# protect_circuit.net
KiCad netlist of a schematic drawn in Altium Designer
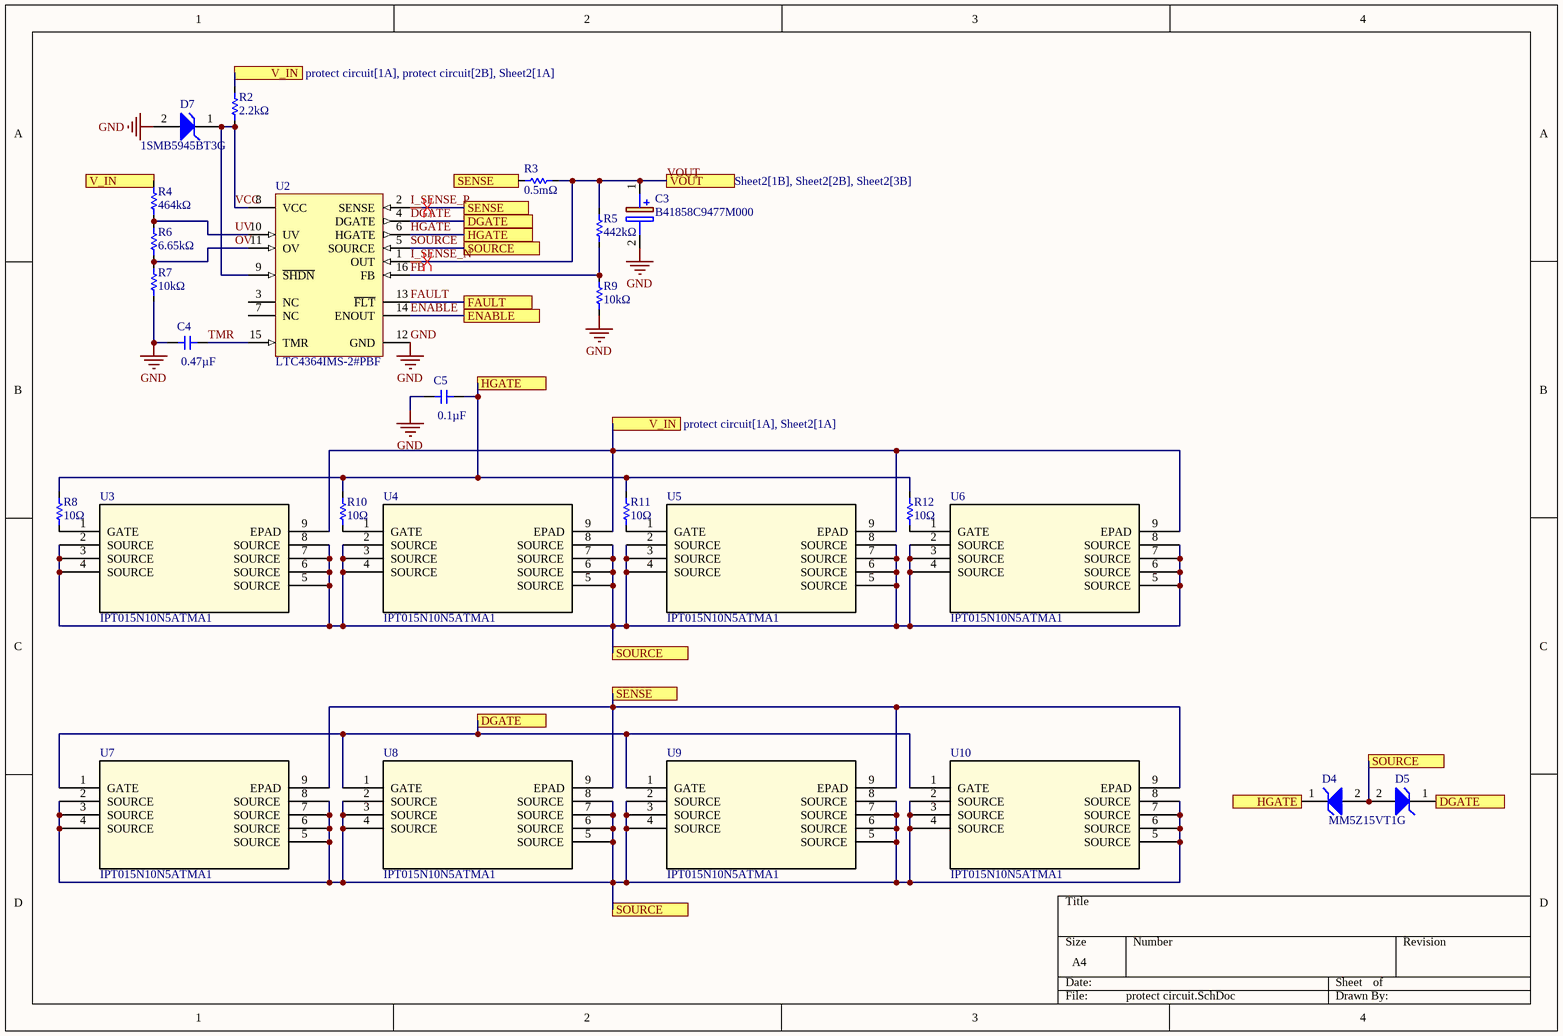
[diagram p0: protect circuit.SchDoc]

(export (version "E")
  (design (tool "Eeschema 10.0.6"))
  (components
    (comp (ref "C3")
      (value "B41858C9477M000")
      (footprint "SamacSys:CAPPRD750W90D1800H3700")
      (description "Capacitor Polarised")
      (fields (field (name "MOUSER PART NUMBER") "871-B41858C9477M"))
      (libsource (lib "*") (part "B41858C9477M000"))
    )
    (comp (ref "C4")
      (value "non-polar_Capacitor")
      (footprint "1210")
      (description "SMD type ceramic capacitor")
      (fields
        (field (name "VOLTAGE") "50V")
        (field (name "CAPACITANCE") "0.47µF")
        (field (name "SOURCE") "robit_passive.SchLib")
      )
      (libsource (lib "robit circuit") (part "Capacitor"))
    )
    (comp (ref "C5")
      (value "non-polar_Capacitor")
      (footprint "1210")
      (description "SMD type ceramic capacitor")
      (fields
        (field (name "VOLTAGE") "50V")
        (field (name "CAPACITANCE") "0.1µF")
        (field (name "SOURCE") "robit_passive.SchLib")
      )
      (libsource (lib "robit circuit") (part "Capacitor"))
    )
    (comp (ref "D4")
      (value "MM5Z15VT1G")
      (footprint "ONSC-SOD-523-2-502-01_V")
      (description "Zener Voltage Regulator, 500 mW, 2-Pin SOD-523, Pb-Free, Tape and Reel")
      (fields (field (name "MANUFACTURER") "On Semiconductor"))
      (libsource (lib "Altium Content Vault") (part "ONSC-K1A2-2"))
    )
    (comp (ref "D5")
      (value "MM5Z15VT1G")
      (footprint "ONSC-SOD-523-2-502-01_V")
      (description "Zener Voltage Regulator, 500 mW, 2-Pin SOD-523, Pb-Free, Tape and Reel")
      (fields (field (name "MANUFACTURER") "On Semiconductor"))
      (libsource (lib "Altium Content Vault") (part "ONSC-K1A2-2"))
    )
    (comp (ref "D7")
      (value "1SMB5945BT3G")
      (footprint "ONSC-SMB-2-403A-03_H_V")
      (description "3 W Zener Voltage Regulator, 2-Pin SMB, Pb-Free, Tape and Reel")
      (fields (field (name "MANUFACTURER") "On Semiconductor"))
      (libsource (lib "Altium Content Vault") (part "ONSC-K1A2-2"))
    )
    (comp (ref "R2") (value "2.2kΩ") (footprint "SMD_2512") (libsource (lib "Resistor") (part "Resistor")))
    (comp (ref "R3") (value "0.5mΩ") (footprint "SMD_2512") (libsource (lib "Resistor") (part "Resistor")))
    (comp (ref "R4") (value "464kΩ") (footprint "SMD_0603") (libsource (lib "Resistor") (part "Resistor")))
    (comp (ref "R5") (value "442kΩ") (footprint "SMD_0603") (libsource (lib "Resistor") (part "Resistor")))
    (comp (ref "R6") (value "6.65kΩ") (footprint "SMD_0603") (libsource (lib "Resistor") (part "Resistor")))
    (comp (ref "R7") (value "10kΩ") (footprint "SMD_0603") (libsource (lib "Resistor") (part "Resistor")))
    (comp (ref "R8") (value "10Ω") (footprint "SMD_0603") (libsource (lib "Resistor") (part "Resistor")))
    (comp (ref "R9") (value "10kΩ") (footprint "SMD_0603") (libsource (lib "Resistor") (part "Resistor")))
    (comp (ref "R10") (value "10Ω") (footprint "SMD_0603") (libsource (lib "Resistor") (part "Resistor")))
    (comp (ref "R11") (value "10Ω") (footprint "SMD_0603") (libsource (lib "Resistor") (part "Resistor")))
    (comp (ref "R12") (value "10Ω") (footprint "SMD_0603") (libsource (lib "Resistor") (part "Resistor")))
    (comp (ref "U2")
      (value "LTC4364IMS-2#PBF")
      (footprint "LT-MS-16_M")
      (description "Surge Stopper with Ideal Diode, 4 to 80 V Vin, 16-pin SOP (MS-16), -40 to 85 degC, Pb-Free")
      (fields (field (name "MANUFACTURER") "Linear Technology"))
      (libsource (lib "Altium Content Vault") (part "LT-LTC4364-S-16"))
    )
    (comp (ref "U3")
      (value "IPT015N10N5ATMA1")
      (footprint "PG-HSOF-8-1_INF")
      (fields (field (name "COPYRIGHT") "Copyright (C) 2025 Ultra Librarian. All rights reserved."))
      (libsource (lib "IPT015N10N5ATMA1") (part "IPT015N10N5ATMA1"))
    )
    (comp (ref "U4")
      (value "IPT015N10N5ATMA1")
      (footprint "PG-HSOF-8-1_INF")
      (fields (field (name "COPYRIGHT") "Copyright (C) 2025 Ultra Librarian. All rights reserved."))
      (libsource (lib "IPT015N10N5ATMA1") (part "IPT015N10N5ATMA1"))
    )
    (comp (ref "U5")
      (value "IPT015N10N5ATMA1")
      (footprint "PG-HSOF-8-1_INF")
      (fields (field (name "COPYRIGHT") "Copyright (C) 2025 Ultra Librarian. All rights reserved."))
      (libsource (lib "IPT015N10N5ATMA1") (part "IPT015N10N5ATMA1"))
    )
    (comp (ref "U6")
      (value "IPT015N10N5ATMA1")
      (footprint "PG-HSOF-8-1_INF")
      (fields (field (name "COPYRIGHT") "Copyright (C) 2025 Ultra Librarian. All rights reserved."))
      (libsource (lib "IPT015N10N5ATMA1") (part "IPT015N10N5ATMA1"))
    )
    (comp (ref "U7")
      (value "IPT015N10N5ATMA1")
      (footprint "PG-HSOF-8-1_INF")
      (fields (field (name "COPYRIGHT") "Copyright (C) 2025 Ultra Librarian. All rights reserved."))
      (libsource (lib "IPT015N10N5ATMA1") (part "IPT015N10N5ATMA1"))
    )
    (comp (ref "U8")
      (value "IPT015N10N5ATMA1")
      (footprint "PG-HSOF-8-1_INF")
      (fields (field (name "COPYRIGHT") "Copyright (C) 2025 Ultra Librarian. All rights reserved."))
      (libsource (lib "IPT015N10N5ATMA1") (part "IPT015N10N5ATMA1"))
    )
    (comp (ref "U9")
      (value "IPT015N10N5ATMA1")
      (footprint "PG-HSOF-8-1_INF")
      (fields (field (name "COPYRIGHT") "Copyright (C) 2025 Ultra Librarian. All rights reserved."))
      (libsource (lib "IPT015N10N5ATMA1") (part "IPT015N10N5ATMA1"))
    )
    (comp (ref "U10")
      (value "IPT015N10N5ATMA1")
      (footprint "PG-HSOF-8-1_INF")
      (fields (field (name "COPYRIGHT") "Copyright (C) 2025 Ultra Librarian. All rights reserved."))
      (libsource (lib "IPT015N10N5ATMA1") (part "IPT015N10N5ATMA1"))
    )
  )
  (nets
    (net (code "1") (name "/DGATE") (class "Default")
      (node (ref "D5") (pin "1") (pinfunction "K_1") (pintype "passive"))
      (node (ref "U10") (pin "1") (pinfunction "GATE_1") (pintype "passive"))
      (node (ref "U2") (pin "4") (pinfunction "DGATE_4") (pintype "output"))
      (node (ref "U7") (pin "1") (pinfunction "GATE_1") (pintype "passive"))
      (node (ref "U8") (pin "1") (pinfunction "GATE_1") (pintype "passive"))
      (node (ref "U9") (pin "1") (pinfunction "GATE_1") (pintype "passive"))
    )
    (net (code "2") (name "/ENABLE") (class "Default")
      (node (ref "U2") (pin "14") (pinfunction "ENOUT_14") (pintype "tri_state"))
    )
    (net (code "3") (name "/FAULT") (class "Default")
      (node (ref "U2") (pin "13") (pinfunction "~{FLT}_13") (pintype "tri_state"))
    )
    (net (code "4") (name "/FB") (class "Default")
      (node (ref "R5") (pin "2") (pinfunction "2_2") (pintype "passive"))
      (node (ref "R9") (pin "1") (pinfunction "1_1") (pintype "passive"))
      (node (ref "U2") (pin "16") (pinfunction "FB_16") (pintype "input"))
    )
    (net (code "5") (name "/HGATE") (class "Default")
      (node (ref "C5") (pin "2") (pinfunction "2_2") (pintype "passive"))
      (node (ref "D4") (pin "1") (pinfunction "K_1") (pintype "passive"))
      (node (ref "R10") (pin "1") (pinfunction "1_1") (pintype "passive"))
      (node (ref "R11") (pin "1") (pinfunction "1_1") (pintype "passive"))
      (node (ref "R12") (pin "1") (pinfunction "1_1") (pintype "passive"))
      (node (ref "R8") (pin "1") (pinfunction "1_1") (pintype "passive"))
      (node (ref "U2") (pin "6") (pinfunction "HGATE_6") (pintype "output"))
    )
    (net (code "6") (name "/I_SENSE_N") (class "Default")
      (node (ref "C3") (pin "1") (pinfunction "+_1") (pintype "passive"))
      (node (ref "R3") (pin "2") (pinfunction "2_2") (pintype "passive"))
      (node (ref "R5") (pin "1") (pinfunction "1_1") (pintype "passive"))
      (node (ref "U2") (pin "1") (pinfunction "OUT_1") (pintype "input"))
    )
    (net (code "7") (name "/I_SENSE_P") (class "Default")
      (node (ref "R3") (pin "1") (pinfunction "1_1") (pintype "passive"))
      (node (ref "U10") (pin "9") (pinfunction "EPAD_9") (pintype "passive"))
      (node (ref "U2") (pin "2") (pinfunction "SENSE_2") (pintype "input"))
      (node (ref "U7") (pin "9") (pinfunction "EPAD_9") (pintype "passive"))
      (node (ref "U8") (pin "9") (pinfunction "EPAD_9") (pintype "passive"))
      (node (ref "U9") (pin "9") (pinfunction "EPAD_9") (pintype "passive"))
    )
    (net (code "8") (name "/OV") (class "Default")
      (node (ref "R6") (pin "2") (pinfunction "2_2") (pintype "passive"))
      (node (ref "R7") (pin "1") (pinfunction "1_1") (pintype "passive"))
      (node (ref "U2") (pin "11") (pinfunction "OV_11") (pintype "input"))
    )
    (net (code "9") (name "/SOURCE") (class "Default")
      (node (ref "D4") (pin "2") (pinfunction "A_2") (pintype "passive"))
      (node (ref "D5") (pin "2") (pinfunction "A_2") (pintype "passive"))
      (node (ref "U10") (pin "2") (pinfunction "SOURCE_2") (pintype "passive"))
      (node (ref "U10") (pin "3") (pinfunction "SOURCE_3") (pintype "passive"))
      (node (ref "U10") (pin "4") (pinfunction "SOURCE_4") (pintype "passive"))
      (node (ref "U10") (pin "5") (pinfunction "SOURCE_5") (pintype "passive"))
      (node (ref "U10") (pin "6") (pinfunction "SOURCE_6") (pintype "passive"))
      (node (ref "U10") (pin "7") (pinfunction "SOURCE_7") (pintype "passive"))
      (node (ref "U10") (pin "8") (pinfunction "SOURCE_8") (pintype "passive"))
      (node (ref "U2") (pin "5") (pinfunction "SOURCE_5") (pintype "input"))
      (node (ref "U3") (pin "2") (pinfunction "SOURCE_2") (pintype "passive"))
      (node (ref "U3") (pin "3") (pinfunction "SOURCE_3") (pintype "passive"))
      (node (ref "U3") (pin "4") (pinfunction "SOURCE_4") (pintype "passive"))
      (node (ref "U3") (pin "5") (pinfunction "SOURCE_5") (pintype "passive"))
      (node (ref "U3") (pin "6") (pinfunction "SOURCE_6") (pintype "passive"))
      (node (ref "U3") (pin "7") (pinfunction "SOURCE_7") (pintype "passive"))
      (node (ref "U3") (pin "8") (pinfunction "SOURCE_8") (pintype "passive"))
      (node (ref "U4") (pin "2") (pinfunction "SOURCE_2") (pintype "passive"))
      (node (ref "U4") (pin "3") (pinfunction "SOURCE_3") (pintype "passive"))
      (node (ref "U4") (pin "4") (pinfunction "SOURCE_4") (pintype "passive"))
      (node (ref "U4") (pin "5") (pinfunction "SOURCE_5") (pintype "passive"))
      (node (ref "U4") (pin "6") (pinfunction "SOURCE_6") (pintype "passive"))
      (node (ref "U4") (pin "7") (pinfunction "SOURCE_7") (pintype "passive"))
      (node (ref "U4") (pin "8") (pinfunction "SOURCE_8") (pintype "passive"))
      (node (ref "U5") (pin "2") (pinfunction "SOURCE_2") (pintype "passive"))
      (node (ref "U5") (pin "3") (pinfunction "SOURCE_3") (pintype "passive"))
      (node (ref "U5") (pin "4") (pinfunction "SOURCE_4") (pintype "passive"))
      (node (ref "U5") (pin "5") (pinfunction "SOURCE_5") (pintype "passive"))
      (node (ref "U5") (pin "6") (pinfunction "SOURCE_6") (pintype "passive"))
      (node (ref "U5") (pin "7") (pinfunction "SOURCE_7") (pintype "passive"))
      (node (ref "U5") (pin "8") (pinfunction "SOURCE_8") (pintype "passive"))
      (node (ref "U6") (pin "2") (pinfunction "SOURCE_2") (pintype "passive"))
      (node (ref "U6") (pin "3") (pinfunction "SOURCE_3") (pintype "passive"))
      (node (ref "U6") (pin "4") (pinfunction "SOURCE_4") (pintype "passive"))
      (node (ref "U6") (pin "5") (pinfunction "SOURCE_5") (pintype "passive"))
      (node (ref "U6") (pin "6") (pinfunction "SOURCE_6") (pintype "passive"))
      (node (ref "U6") (pin "7") (pinfunction "SOURCE_7") (pintype "passive"))
      (node (ref "U6") (pin "8") (pinfunction "SOURCE_8") (pintype "passive"))
      (node (ref "U7") (pin "2") (pinfunction "SOURCE_2") (pintype "passive"))
      (node (ref "U7") (pin "3") (pinfunction "SOURCE_3") (pintype "passive"))
      (node (ref "U7") (pin "4") (pinfunction "SOURCE_4") (pintype "passive"))
      (node (ref "U7") (pin "5") (pinfunction "SOURCE_5") (pintype "passive"))
      (node (ref "U7") (pin "6") (pinfunction "SOURCE_6") (pintype "passive"))
      (node (ref "U7") (pin "7") (pinfunction "SOURCE_7") (pintype "passive"))
      (node (ref "U7") (pin "8") (pinfunction "SOURCE_8") (pintype "passive"))
      (node (ref "U8") (pin "2") (pinfunction "SOURCE_2") (pintype "passive"))
      (node (ref "U8") (pin "3") (pinfunction "SOURCE_3") (pintype "passive"))
      (node (ref "U8") (pin "4") (pinfunction "SOURCE_4") (pintype "passive"))
      (node (ref "U8") (pin "5") (pinfunction "SOURCE_5") (pintype "passive"))
      (node (ref "U8") (pin "6") (pinfunction "SOURCE_6") (pintype "passive"))
      (node (ref "U8") (pin "7") (pinfunction "SOURCE_7") (pintype "passive"))
      (node (ref "U8") (pin "8") (pinfunction "SOURCE_8") (pintype "passive"))
      (node (ref "U9") (pin "2") (pinfunction "SOURCE_2") (pintype "passive"))
      (node (ref "U9") (pin "3") (pinfunction "SOURCE_3") (pintype "passive"))
      (node (ref "U9") (pin "4") (pinfunction "SOURCE_4") (pintype "passive"))
      (node (ref "U9") (pin "5") (pinfunction "SOURCE_5") (pintype "passive"))
      (node (ref "U9") (pin "6") (pinfunction "SOURCE_6") (pintype "passive"))
      (node (ref "U9") (pin "7") (pinfunction "SOURCE_7") (pintype "passive"))
      (node (ref "U9") (pin "8") (pinfunction "SOURCE_8") (pintype "passive"))
    )
    (net (code "10") (name "/TMR") (class "Default")
      (node (ref "C4") (pin "2") (pinfunction "2_2") (pintype "passive"))
      (node (ref "U2") (pin "15") (pinfunction "TMR_15") (pintype "input"))
    )
    (net (code "11") (name "/UV") (class "Default")
      (node (ref "R4") (pin "2") (pinfunction "2_2") (pintype "passive"))
      (node (ref "R6") (pin "1") (pinfunction "1_1") (pintype "passive"))
      (node (ref "U2") (pin "10") (pinfunction "UV_10") (pintype "input"))
    )
    (net (code "12") (name "/VCC") (class "Default")
      (node (ref "D7") (pin "1") (pinfunction "K_1") (pintype "passive"))
      (node (ref "R2") (pin "2") (pinfunction "2_2") (pintype "passive"))
      (node (ref "U2") (pin "8") (pinfunction "VCC_8") (pintype "power_in"))
      (node (ref "U2") (pin "9") (pinfunction "~{SHDN}_9") (pintype "input"))
    )
    (net (code "13") (name "/V_IN") (class "Default")
      (node (ref "R2") (pin "1") (pinfunction "1_1") (pintype "passive"))
      (node (ref "R4") (pin "1") (pinfunction "1_1") (pintype "passive"))
      (node (ref "U3") (pin "9") (pinfunction "EPAD_9") (pintype "passive"))
      (node (ref "U4") (pin "9") (pinfunction "EPAD_9") (pintype "passive"))
      (node (ref "U5") (pin "9") (pinfunction "EPAD_9") (pintype "passive"))
      (node (ref "U6") (pin "9") (pinfunction "EPAD_9") (pintype "passive"))
    )
    (net (code "14") (name "GND") (class "Default")
      (node (ref "C3") (pin "2") (pinfunction "-_2") (pintype "passive"))
      (node (ref "C4") (pin "1") (pinfunction "1_1") (pintype "passive"))
      (node (ref "C5") (pin "1") (pinfunction "1_1") (pintype "passive"))
      (node (ref "D7") (pin "2") (pinfunction "A_2") (pintype "passive"))
      (node (ref "R7") (pin "2") (pinfunction "2_2") (pintype "passive"))
      (node (ref "R9") (pin "2") (pinfunction "2_2") (pintype "passive"))
      (node (ref "U2") (pin "12") (pinfunction "GND_12") (pintype "power_in"))
    )
    (net (code "15") (name "Net-(U3-GATE)") (class "Default")
      (node (ref "R8") (pin "2") (pinfunction "2_2") (pintype "passive"))
      (node (ref "U3") (pin "1") (pinfunction "GATE_1") (pintype "passive"))
    )
    (net (code "16") (name "Net-(U4-GATE)") (class "Default")
      (node (ref "R10") (pin "2") (pinfunction "2_2") (pintype "passive"))
      (node (ref "U4") (pin "1") (pinfunction "GATE_1") (pintype "passive"))
    )
    (net (code "17") (name "Net-(U5-GATE)") (class "Default")
      (node (ref "R11") (pin "2") (pinfunction "2_2") (pintype "passive"))
      (node (ref "U5") (pin "1") (pinfunction "GATE_1") (pintype "passive"))
    )
    (net (code "18") (name "Net-(U6-GATE)") (class "Default")
      (node (ref "R12") (pin "2") (pinfunction "2_2") (pintype "passive"))
      (node (ref "U6") (pin "1") (pinfunction "GATE_1") (pintype "passive"))
    )
    (net (code "19") (name "unconnected-(U2-NC-Pad3)") (class "Default")
      (node (ref "U2") (pin "3") (pinfunction "NC_3") (pintype "passive"))
    )
    (net (code "20") (name "unconnected-(U2-NC-Pad7)") (class "Default")
      (node (ref "U2") (pin "7") (pinfunction "NC_7") (pintype "passive"))
    )
  )
)
